# Relays.net
KiCad netlist of a schematic drawn in Altium Designer
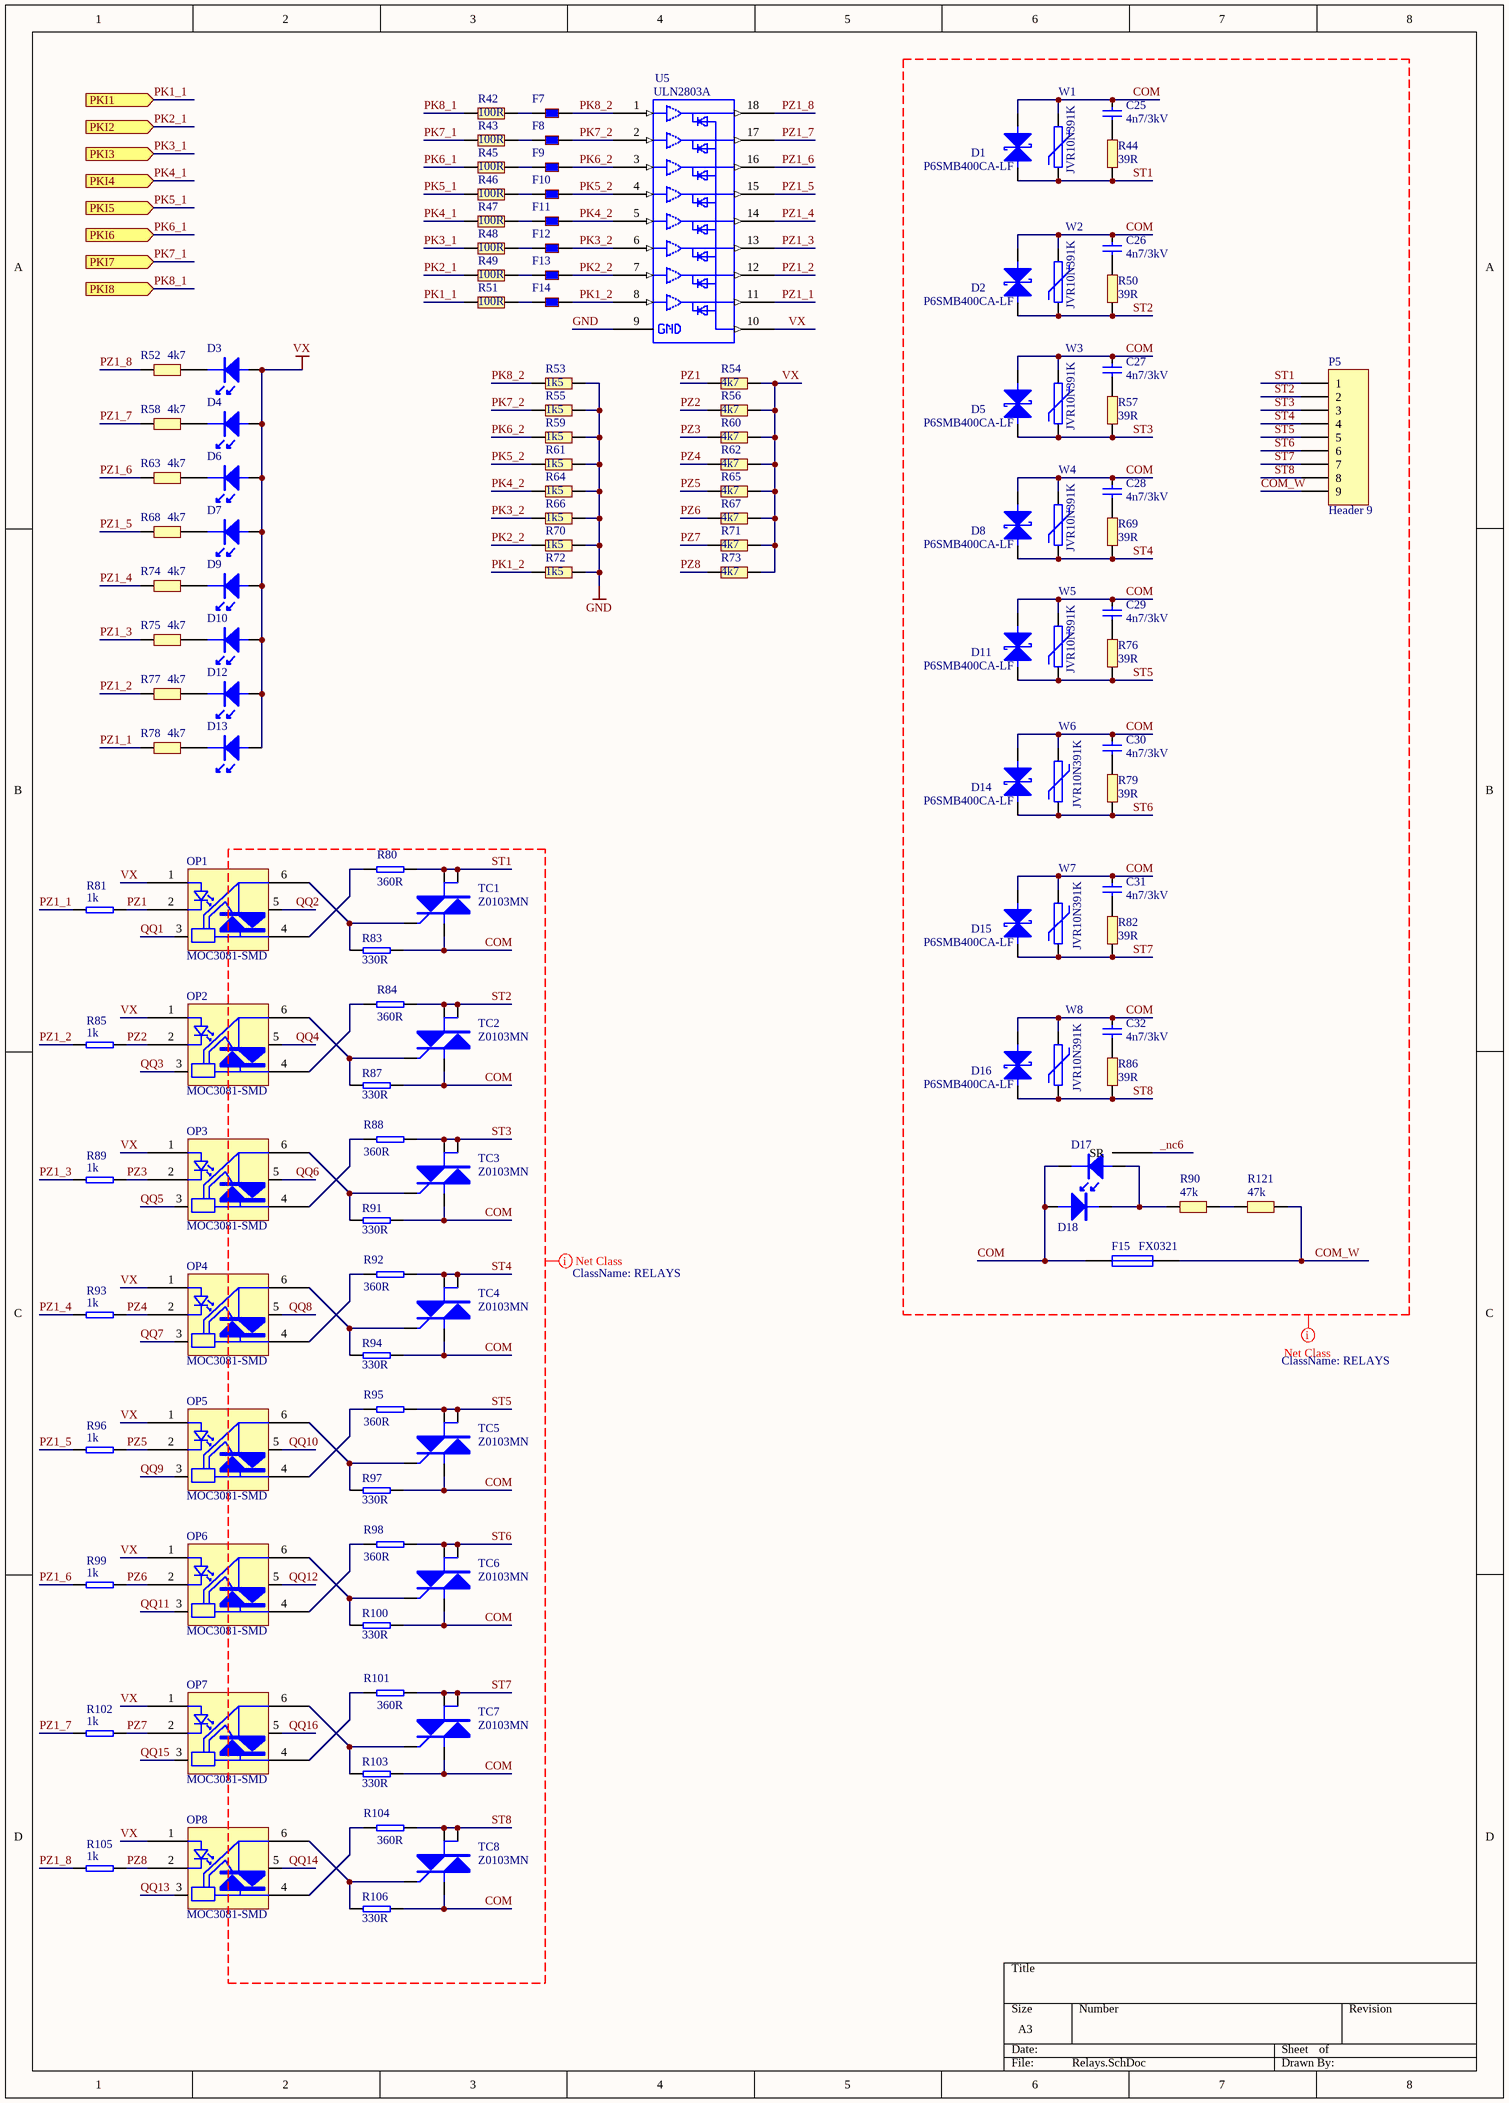
[diagram p0: Relays.SchDoc]

(export (version "E")
  (design (tool "Eeschema 10.0.6"))
  (components
    (comp (ref "C25") (value "4n7/3kV") (footprint "CAP_75") (libsource (lib "*") (part "CAP")))
    (comp (ref "C26") (value "4n7/3kV") (footprint "CAP_75") (libsource (lib "*") (part "CAP")))
    (comp (ref "C27") (value "4n7/3kV") (footprint "CAP_75") (libsource (lib "*") (part "CAP")))
    (comp (ref "C28") (value "4n7/3kV") (footprint "CAP_75") (libsource (lib "*") (part "CAP")))
    (comp (ref "C29") (value "4n7/3kV") (footprint "CAP_75") (libsource (lib "*") (part "CAP")))
    (comp (ref "C30") (value "4n7/3kV") (footprint "CAP_75") (libsource (lib "*") (part "CAP")))
    (comp (ref "C31") (value "4n7/3kV") (footprint "CAP_75") (libsource (lib "*") (part "CAP")))
    (comp (ref "C32") (value "4n7/3kV") (footprint "CAP_75") (libsource (lib "*") (part "CAP")))
    (comp (ref "D1")
      (value "P6SMB400CA-LF")
      (footprint "RD5_U")
      (libsource (lib "ElhosSchLib") (part "TRANSIL"))
    )
    (comp (ref "D2")
      (value "P6SMB400CA-LF")
      (footprint "RD5_U")
      (libsource (lib "ElhosSchLib") (part "TRANSIL"))
    )
    (comp (ref "D3") (value "LED1") (footprint "0805LB") (libsource (lib "ElhosSchLib") (part "LED1")))
    (comp (ref "D4") (value "LED1") (footprint "0805LB") (libsource (lib "ElhosSchLib") (part "LED1")))
    (comp (ref "D5")
      (value "P6SMB400CA-LF")
      (footprint "RD5_U")
      (libsource (lib "ElhosSchLib") (part "TRANSIL"))
    )
    (comp (ref "D6") (value "LED1") (footprint "0805LB") (libsource (lib "ElhosSchLib") (part "LED1")))
    (comp (ref "D7") (value "LED1") (footprint "0805LB") (libsource (lib "ElhosSchLib") (part "LED1")))
    (comp (ref "D8")
      (value "P6SMB400CA-LF")
      (footprint "RD5_U")
      (libsource (lib "ElhosSchLib") (part "TRANSIL"))
    )
    (comp (ref "D9") (value "LED1") (footprint "0805LB") (libsource (lib "ElhosSchLib") (part "LED1")))
    (comp (ref "D10") (value "LED1") (footprint "0805LB") (libsource (lib "ElhosSchLib") (part "LED1")))
    (comp (ref "D11")
      (value "P6SMB400CA-LF")
      (footprint "RD5_U")
      (libsource (lib "ElhosSchLib") (part "TRANSIL"))
    )
    (comp (ref "D12") (value "LED1") (footprint "0805LB") (libsource (lib "ElhosSchLib") (part "LED1")))
    (comp (ref "D13") (value "LED1") (footprint "0805LB") (libsource (lib "ElhosSchLib") (part "LED1")))
    (comp (ref "D14")
      (value "P6SMB400CA-LF")
      (footprint "RD5_U")
      (libsource (lib "ElhosSchLib") (part "TRANSIL"))
    )
    (comp (ref "D15")
      (value "P6SMB400CA-LF")
      (footprint "RD5_U")
      (libsource (lib "ElhosSchLib") (part "TRANSIL"))
    )
    (comp (ref "D16")
      (value "P6SMB400CA-LF")
      (footprint "RD5_U")
      (libsource (lib "ElhosSchLib") (part "TRANSIL"))
    )
    (comp (ref "D17") (value "LED1") (footprint "LED_LAMP_1") (libsource (lib "") (part "LED1_1")))
    (comp (ref "D18")
      (value "1N4148-0805")
      (footprint "0805D")
      (description "Diode")
      (libsource (lib "*") (part "DIODE1"))
    )
    (comp (ref "F7")
      (value "BLM18AG102SN1D")
      (footprint "0603L")
      (description "Koralik ferrytowy")
      (libsource (lib "*") (part "KORALIK"))
    )
    (comp (ref "F8")
      (value "BLM18AG102SN1D")
      (footprint "0603L")
      (description "Koralik ferrytowy")
      (libsource (lib "*") (part "KORALIK"))
    )
    (comp (ref "F9")
      (value "BLM18AG102SN1D")
      (footprint "0603L")
      (description "Koralik ferrytowy")
      (libsource (lib "*") (part "KORALIK"))
    )
    (comp (ref "F10")
      (value "BLM18AG102SN1D")
      (footprint "0603L")
      (description "Koralik ferrytowy")
      (libsource (lib "*") (part "KORALIK"))
    )
    (comp (ref "F11")
      (value "BLM18AG102SN1D")
      (footprint "0603L")
      (description "Koralik ferrytowy")
      (libsource (lib "*") (part "KORALIK"))
    )
    (comp (ref "F12")
      (value "BLM18AG102SN1D")
      (footprint "0603L")
      (description "Koralik ferrytowy")
      (libsource (lib "*") (part "KORALIK"))
    )
    (comp (ref "F13")
      (value "BLM18AG102SN1D")
      (footprint "0603L")
      (description "Koralik ferrytowy")
      (libsource (lib "*") (part "KORALIK"))
    )
    (comp (ref "F14")
      (value "BLM18AG102SN1D")
      (footprint "0603L")
      (description "Koralik ferrytowy")
      (libsource (lib "*") (part "KORALIK"))
    )
    (comp (ref "F15")
      (value "FX0321")
      (footprint "FX300")
      (description "Fuse")
      (libsource (lib "*") (part "FUSE1"))
    )
    (comp (ref "OP1")
      (value "MOC3081-SMD")
      (footprint "SMD6-OP")
      (libsource (lib "ElhosSchLib") (part "MOC3041"))
    )
    (comp (ref "OP2")
      (value "MOC3081-SMD")
      (footprint "SMD6-OP")
      (libsource (lib "ElhosSchLib") (part "MOC3041"))
    )
    (comp (ref "OP3")
      (value "MOC3081-SMD")
      (footprint "SMD6-OP")
      (libsource (lib "ElhosSchLib") (part "MOC3041"))
    )
    (comp (ref "OP4")
      (value "MOC3081-SMD")
      (footprint "SMD6-OP")
      (libsource (lib "ElhosSchLib") (part "MOC3041"))
    )
    (comp (ref "OP5")
      (value "MOC3081-SMD")
      (footprint "SMD6-OP")
      (libsource (lib "ElhosSchLib") (part "MOC3041"))
    )
    (comp (ref "OP6")
      (value "MOC3081-SMD")
      (footprint "SMD6-OP")
      (libsource (lib "ElhosSchLib") (part "MOC3041"))
    )
    (comp (ref "OP7")
      (value "MOC3081-SMD")
      (footprint "SMD6-OP")
      (libsource (lib "ElhosSchLib") (part "MOC3041"))
    )
    (comp (ref "OP8")
      (value "MOC3081-SMD")
      (footprint "SMD6-OP")
      (libsource (lib "ElhosSchLib") (part "MOC3041"))
    )
    (comp (ref "P5")
      (value "Header 9")
      (description "Header, 9-Pin")
      (fields (field (name "PUBLISHER") "Altium Limited"))
      (libsource (lib "Miscellaneous Connectors") (part "Header 9"))
    )
    (comp (ref "R42") (value "100R") (footprint "0603R") (libsource (lib "") (part "RES3_1")))
    (comp (ref "R43") (value "100R") (footprint "0603R") (libsource (lib "") (part "RES3_1")))
    (comp (ref "R44") (value "39R") (footprint "1206") (libsource (lib "") (part "RES3_2")))
    (comp (ref "R45") (value "100R") (footprint "0603R") (libsource (lib "") (part "RES3_1")))
    (comp (ref "R46") (value "100R") (footprint "0603R") (libsource (lib "") (part "RES3_1")))
    (comp (ref "R47") (value "100R") (footprint "0603R") (libsource (lib "") (part "RES3_1")))
    (comp (ref "R48") (value "100R") (footprint "0603R") (libsource (lib "") (part "RES3_1")))
    (comp (ref "R49") (value "100R") (footprint "0603R") (libsource (lib "") (part "RES3_1")))
    (comp (ref "R50") (value "39R") (footprint "1206") (libsource (lib "") (part "RES3_2")))
    (comp (ref "R51") (value "100R") (footprint "0603R") (libsource (lib "") (part "RES3_1")))
    (comp (ref "R52") (value "4k7") (footprint "0603R") (libsource (lib "") (part "RES3_1")))
    (comp (ref "R53") (value "1k5") (footprint "0603R") (libsource (lib "") (part "RES3_1")))
    (comp (ref "R54") (value "4k7") (footprint "0603R") (libsource (lib "") (part "RES3_1")))
    (comp (ref "R55") (value "1k5") (footprint "0603R") (libsource (lib "") (part "RES3_1")))
    (comp (ref "R56") (value "4k7") (footprint "0603R") (libsource (lib "") (part "RES3_1")))
    (comp (ref "R57") (value "39R") (footprint "1206") (libsource (lib "") (part "RES3_2")))
    (comp (ref "R58") (value "4k7") (footprint "0603R") (libsource (lib "") (part "RES3_1")))
    (comp (ref "R59") (value "1k5") (footprint "0603R") (libsource (lib "") (part "RES3_1")))
    (comp (ref "R60") (value "4k7") (footprint "0603R") (libsource (lib "") (part "RES3_1")))
    (comp (ref "R61") (value "1k5") (footprint "0603R") (libsource (lib "") (part "RES3_1")))
    (comp (ref "R62") (value "4k7") (footprint "0603R") (libsource (lib "") (part "RES3_1")))
    (comp (ref "R63") (value "4k7") (footprint "0603R") (libsource (lib "") (part "RES3_1")))
    (comp (ref "R64") (value "1k5") (footprint "0603R") (libsource (lib "") (part "RES3_1")))
    (comp (ref "R65") (value "4k7") (footprint "0603R") (libsource (lib "") (part "RES3_1")))
    (comp (ref "R66") (value "1k5") (footprint "0603R") (libsource (lib "") (part "RES3_1")))
    (comp (ref "R67") (value "4k7") (footprint "0603R") (libsource (lib "") (part "RES3_1")))
    (comp (ref "R68") (value "4k7") (footprint "0603R") (libsource (lib "") (part "RES3_1")))
    (comp (ref "R69") (value "39R") (footprint "1206") (libsource (lib "") (part "RES3_2")))
    (comp (ref "R70") (value "1k5") (footprint "0603R") (libsource (lib "") (part "RES3_1")))
    (comp (ref "R71") (value "4k7") (footprint "0603R") (libsource (lib "") (part "RES3_1")))
    (comp (ref "R72") (value "1k5") (footprint "0603R") (libsource (lib "") (part "RES3_1")))
    (comp (ref "R73") (value "4k7") (footprint "0603R") (libsource (lib "") (part "RES3_1")))
    (comp (ref "R74") (value "4k7") (footprint "0603R") (libsource (lib "") (part "RES3_1")))
    (comp (ref "R75") (value "4k7") (footprint "0603R") (libsource (lib "") (part "RES3_1")))
    (comp (ref "R76") (value "39R") (footprint "1206") (libsource (lib "") (part "RES3_2")))
    (comp (ref "R77") (value "4k7") (footprint "0603R") (libsource (lib "") (part "RES3_1")))
    (comp (ref "R78") (value "4k7") (footprint "0603R") (libsource (lib "") (part "RES3_1")))
    (comp (ref "R79") (value "39R") (footprint "1206") (libsource (lib "") (part "RES3_2")))
    (comp (ref "R80") (value "360R") (footprint "0805R") (libsource (lib "*") (part "RES3")))
    (comp (ref "R81") (value "1k") (footprint "0603R") (libsource (lib "*") (part "RES3")))
    (comp (ref "R82") (value "39R") (footprint "1206") (libsource (lib "") (part "RES3_2")))
    (comp (ref "R83") (value "330R") (footprint "0805R") (libsource (lib "*") (part "RES3")))
    (comp (ref "R84") (value "360R") (footprint "0805R") (libsource (lib "*") (part "RES3")))
    (comp (ref "R85") (value "1k") (footprint "0603R") (libsource (lib "*") (part "RES3")))
    (comp (ref "R86") (value "39R") (footprint "1206") (libsource (lib "") (part "RES3_2")))
    (comp (ref "R87") (value "330R") (footprint "0805R") (libsource (lib "*") (part "RES3")))
    (comp (ref "R88") (value "360R") (footprint "0805R") (libsource (lib "*") (part "RES3")))
    (comp (ref "R89") (value "1k") (footprint "0603R") (libsource (lib "*") (part "RES3")))
    (comp (ref "R90") (value "47k") (footprint "1206") (libsource (lib "") (part "RES3_1")))
    (comp (ref "R91") (value "330R") (footprint "0805R") (libsource (lib "*") (part "RES3")))
    (comp (ref "R92") (value "360R") (footprint "0805R") (libsource (lib "*") (part "RES3")))
    (comp (ref "R93") (value "1k") (footprint "0603R") (libsource (lib "*") (part "RES3")))
    (comp (ref "R94") (value "330R") (footprint "0805R") (libsource (lib "*") (part "RES3")))
    (comp (ref "R95") (value "360R") (footprint "0805R") (libsource (lib "*") (part "RES3")))
    (comp (ref "R96") (value "1k") (footprint "0603R") (libsource (lib "*") (part "RES3")))
    (comp (ref "R97") (value "330R") (footprint "0805R") (libsource (lib "*") (part "RES3")))
    (comp (ref "R98") (value "360R") (footprint "0805R") (libsource (lib "*") (part "RES3")))
    (comp (ref "R99") (value "1k") (footprint "0603R") (libsource (lib "*") (part "RES3")))
    (comp (ref "R100") (value "330R") (footprint "0805R") (libsource (lib "*") (part "RES3")))
    (comp (ref "R101") (value "360R") (footprint "0805R") (libsource (lib "*") (part "RES3")))
    (comp (ref "R102") (value "1k") (footprint "0603R") (libsource (lib "*") (part "RES3")))
    (comp (ref "R103") (value "330R") (footprint "0805R") (libsource (lib "*") (part "RES3")))
    (comp (ref "R104") (value "360R") (footprint "0805R") (libsource (lib "*") (part "RES3")))
    (comp (ref "R105") (value "1k") (footprint "0603R") (libsource (lib "*") (part "RES3")))
    (comp (ref "R106") (value "330R") (footprint "0805R") (libsource (lib "*") (part "RES3")))
    (comp (ref "R121") (value "47k") (footprint "1206") (libsource (lib "") (part "RES3_1")))
    (comp (ref "TC1") (value "Z0103MN") (footprint "SOT223") (libsource (lib "*") (part "Z0103MN")))
    (comp (ref "TC2") (value "Z0103MN") (footprint "SOT223") (libsource (lib "*") (part "Z0103MN")))
    (comp (ref "TC3") (value "Z0103MN") (footprint "SOT223") (libsource (lib "*") (part "Z0103MN")))
    (comp (ref "TC4") (value "Z0103MN") (footprint "SOT223") (libsource (lib "*") (part "Z0103MN")))
    (comp (ref "TC5") (value "Z0103MN") (footprint "SOT223") (libsource (lib "*") (part "Z0103MN")))
    (comp (ref "TC6") (value "Z0103MN") (footprint "SOT223") (libsource (lib "*") (part "Z0103MN")))
    (comp (ref "TC7") (value "Z0103MN") (footprint "SOT223") (libsource (lib "*") (part "Z0103MN")))
    (comp (ref "TC8") (value "Z0103MN") (footprint "SOT223") (libsource (lib "*") (part "Z0103MN")))
    (comp (ref "U5")
      (value "ULN2803A")
      (footprint "SO-18")
      (libsource (lib "*") (part "Pro31.tmp_ULN2803A_42"))
    )
    (comp (ref "W1") (value "JVR10N391K") (footprint "CAP_75") (libsource (lib "*") (part "RES4")))
    (comp (ref "W2") (value "JVR10N391K") (footprint "CAP_75") (libsource (lib "*") (part "RES4")))
    (comp (ref "W3") (value "JVR10N391K") (footprint "CAP_75") (libsource (lib "*") (part "RES4")))
    (comp (ref "W4") (value "JVR10N391K") (footprint "CAP_75") (libsource (lib "*") (part "RES4")))
    (comp (ref "W5") (value "JVR10N391K") (footprint "CAP_75") (libsource (lib "*") (part "RES4")))
    (comp (ref "W6") (value "JVR10N391K") (footprint "CAP_75") (libsource (lib "*") (part "RES4")))
    (comp (ref "W7") (value "JVR10N391K") (footprint "CAP_75") (libsource (lib "*") (part "RES4")))
    (comp (ref "W8") (value "JVR10N391K") (footprint "CAP_75") (libsource (lib "*") (part "RES4")))
  )
  (nets
    (net (code "1") (name "/COM") (class "Default")
      (node (ref "C25") (pin "2") (pintype "passive"))
      (node (ref "C26") (pin "2") (pintype "passive"))
      (node (ref "C27") (pin "2") (pintype "passive"))
      (node (ref "C28") (pin "2") (pintype "passive"))
      (node (ref "C29") (pin "2") (pintype "passive"))
      (node (ref "C30") (pin "2") (pintype "passive"))
      (node (ref "C31") (pin "2") (pintype "passive"))
      (node (ref "C32") (pin "2") (pintype "passive"))
      (node (ref "D1") (pin "K") (pinfunction "K_K") (pintype "passive"))
      (node (ref "D11") (pin "K") (pinfunction "K_K") (pintype "passive"))
      (node (ref "D14") (pin "K") (pinfunction "K_K") (pintype "passive"))
      (node (ref "D15") (pin "K") (pinfunction "K_K") (pintype "passive"))
      (node (ref "D16") (pin "K") (pinfunction "K_K") (pintype "passive"))
      (node (ref "D17") (pin "K") (pinfunction "2_K") (pintype "passive"))
      (node (ref "D18") (pin "A") (pinfunction "A_A") (pintype "passive"))
      (node (ref "D2") (pin "K") (pinfunction "K_K") (pintype "passive"))
      (node (ref "D5") (pin "K") (pinfunction "K_K") (pintype "passive"))
      (node (ref "D8") (pin "K") (pinfunction "K_K") (pintype "passive"))
      (node (ref "F15") (pin "1") (pinfunction "1_1") (pintype "passive"))
      (node (ref "R100") (pin "1") (pintype "passive"))
      (node (ref "R103") (pin "1") (pintype "passive"))
      (node (ref "R106") (pin "1") (pintype "passive"))
      (node (ref "R83") (pin "1") (pintype "passive"))
      (node (ref "R87") (pin "1") (pintype "passive"))
      (node (ref "R91") (pin "1") (pintype "passive"))
      (node (ref "R94") (pin "1") (pintype "passive"))
      (node (ref "R97") (pin "1") (pintype "passive"))
      (node (ref "TC1") (pin "1") (pintype "passive"))
      (node (ref "TC2") (pin "1") (pintype "passive"))
      (node (ref "TC3") (pin "1") (pintype "passive"))
      (node (ref "TC4") (pin "1") (pintype "passive"))
      (node (ref "TC5") (pin "1") (pintype "passive"))
      (node (ref "TC6") (pin "1") (pintype "passive"))
      (node (ref "TC7") (pin "1") (pintype "passive"))
      (node (ref "TC8") (pin "1") (pintype "passive"))
      (node (ref "W1") (pin "1") (pintype "passive"))
      (node (ref "W2") (pin "1") (pintype "passive"))
      (node (ref "W3") (pin "1") (pintype "passive"))
      (node (ref "W4") (pin "1") (pintype "passive"))
      (node (ref "W5") (pin "1") (pintype "passive"))
      (node (ref "W6") (pin "1") (pintype "passive"))
      (node (ref "W7") (pin "1") (pintype "passive"))
      (node (ref "W8") (pin "1") (pintype "passive"))
    )
    (net (code "2") (name "/COM_W") (class "Default")
      (node (ref "F15") (pin "2") (pinfunction "2_2") (pintype "passive"))
      (node (ref "P5") (pin "9") (pinfunction "9_9") (pintype "passive"))
      (node (ref "R121") (pin "1") (pintype "passive"))
    )
    (net (code "3") (name "/PK1_1") (class "Default") (node (ref "R51") (pin "2") (pintype "passive")))
    (net (code "4") (name "/PK1_2") (class "Default")
      (node (ref "F14") (pin "2") (pintype "passive"))
      (node (ref "R72") (pin "2") (pintype "passive"))
      (node (ref "U5") (pin "8") (pintype "input"))
    )
    (net (code "5") (name "/PK2_1") (class "Default") (node (ref "R49") (pin "2") (pintype "passive")))
    (net (code "6") (name "/PK2_2") (class "Default")
      (node (ref "F13") (pin "2") (pintype "passive"))
      (node (ref "R70") (pin "2") (pintype "passive"))
      (node (ref "U5") (pin "7") (pintype "input"))
    )
    (net (code "7") (name "/PK3_1") (class "Default") (node (ref "R48") (pin "2") (pintype "passive")))
    (net (code "8") (name "/PK3_2") (class "Default")
      (node (ref "F12") (pin "2") (pintype "passive"))
      (node (ref "R66") (pin "2") (pintype "passive"))
      (node (ref "U5") (pin "6") (pintype "input"))
    )
    (net (code "9") (name "/PK4_1") (class "Default") (node (ref "R47") (pin "2") (pintype "passive")))
    (net (code "10") (name "/PK4_2") (class "Default")
      (node (ref "F11") (pin "2") (pintype "passive"))
      (node (ref "R64") (pin "2") (pintype "passive"))
      (node (ref "U5") (pin "5") (pintype "input"))
    )
    (net (code "11") (name "/PK5_1") (class "Default") (node (ref "R46") (pin "2") (pintype "passive")))
    (net (code "12") (name "/PK5_2") (class "Default")
      (node (ref "F10") (pin "2") (pintype "passive"))
      (node (ref "R61") (pin "2") (pintype "passive"))
      (node (ref "U5") (pin "4") (pintype "input"))
    )
    (net (code "13") (name "/PK6_1") (class "Default") (node (ref "R45") (pin "2") (pintype "passive")))
    (net (code "14") (name "/PK6_2") (class "Default")
      (node (ref "F9") (pin "2") (pintype "passive"))
      (node (ref "R59") (pin "2") (pintype "passive"))
      (node (ref "U5") (pin "3") (pintype "input"))
    )
    (net (code "15") (name "/PK7_1") (class "Default") (node (ref "R43") (pin "2") (pintype "passive")))
    (net (code "16") (name "/PK7_2") (class "Default")
      (node (ref "F8") (pin "2") (pintype "passive"))
      (node (ref "R55") (pin "2") (pintype "passive"))
      (node (ref "U5") (pin "2") (pintype "input"))
    )
    (net (code "17") (name "/PK8_1") (class "Default") (node (ref "R42") (pin "2") (pintype "passive")))
    (net (code "18") (name "/PK8_2") (class "Default")
      (node (ref "F7") (pin "2") (pintype "passive"))
      (node (ref "R53") (pin "2") (pintype "passive"))
      (node (ref "U5") (pin "1") (pintype "input"))
    )
    (net (code "19") (name "/PZ1") (class "Default")
      (node (ref "OP1") (pin "2") (pintype "passive"))
      (node (ref "R54") (pin "2") (pintype "passive"))
      (node (ref "R81") (pin "2") (pintype "passive"))
    )
    (net (code "20") (name "/PZ1_1") (class "Default")
      (node (ref "R78") (pin "2") (pintype "passive"))
      (node (ref "R81") (pin "1") (pintype "passive"))
      (node (ref "U5") (pin "11") (pintype "output"))
    )
    (net (code "21") (name "/PZ1_2") (class "Default")
      (node (ref "R77") (pin "2") (pintype "passive"))
      (node (ref "R85") (pin "1") (pintype "passive"))
      (node (ref "U5") (pin "12") (pintype "output"))
    )
    (net (code "22") (name "/PZ1_3") (class "Default")
      (node (ref "R75") (pin "2") (pintype "passive"))
      (node (ref "R89") (pin "1") (pintype "passive"))
      (node (ref "U5") (pin "13") (pintype "output"))
    )
    (net (code "23") (name "/PZ1_4") (class "Default")
      (node (ref "R74") (pin "2") (pintype "passive"))
      (node (ref "R93") (pin "1") (pintype "passive"))
      (node (ref "U5") (pin "14") (pintype "output"))
    )
    (net (code "24") (name "/PZ1_5") (class "Default")
      (node (ref "R68") (pin "2") (pintype "passive"))
      (node (ref "R96") (pin "1") (pintype "passive"))
      (node (ref "U5") (pin "15") (pintype "output"))
    )
    (net (code "25") (name "/PZ1_6") (class "Default")
      (node (ref "R63") (pin "2") (pintype "passive"))
      (node (ref "R99") (pin "1") (pintype "passive"))
      (node (ref "U5") (pin "16") (pintype "output"))
    )
    (net (code "26") (name "/PZ1_7") (class "Default")
      (node (ref "R102") (pin "1") (pintype "passive"))
      (node (ref "R58") (pin "2") (pintype "passive"))
      (node (ref "U5") (pin "17") (pintype "output"))
    )
    (net (code "27") (name "/PZ1_8") (class "Default")
      (node (ref "R105") (pin "1") (pintype "passive"))
      (node (ref "R52") (pin "2") (pintype "passive"))
      (node (ref "U5") (pin "18") (pintype "output"))
    )
    (net (code "28") (name "/PZ2") (class "Default")
      (node (ref "OP2") (pin "2") (pintype "passive"))
      (node (ref "R56") (pin "2") (pintype "passive"))
      (node (ref "R85") (pin "2") (pintype "passive"))
    )
    (net (code "29") (name "/PZ3") (class "Default")
      (node (ref "OP3") (pin "2") (pintype "passive"))
      (node (ref "R60") (pin "2") (pintype "passive"))
      (node (ref "R89") (pin "2") (pintype "passive"))
    )
    (net (code "30") (name "/PZ4") (class "Default")
      (node (ref "OP4") (pin "2") (pintype "passive"))
      (node (ref "R62") (pin "2") (pintype "passive"))
      (node (ref "R93") (pin "2") (pintype "passive"))
    )
    (net (code "31") (name "/PZ5") (class "Default")
      (node (ref "OP5") (pin "2") (pintype "passive"))
      (node (ref "R65") (pin "2") (pintype "passive"))
      (node (ref "R96") (pin "2") (pintype "passive"))
    )
    (net (code "32") (name "/PZ6") (class "Default")
      (node (ref "OP6") (pin "2") (pintype "passive"))
      (node (ref "R67") (pin "2") (pintype "passive"))
      (node (ref "R99") (pin "2") (pintype "passive"))
    )
    (net (code "33") (name "/PZ7") (class "Default")
      (node (ref "OP7") (pin "2") (pintype "passive"))
      (node (ref "R102") (pin "2") (pintype "passive"))
      (node (ref "R71") (pin "2") (pintype "passive"))
    )
    (net (code "34") (name "/PZ8") (class "Default")
      (node (ref "OP8") (pin "2") (pintype "passive"))
      (node (ref "R105") (pin "2") (pintype "passive"))
      (node (ref "R73") (pin "2") (pintype "passive"))
    )
    (net (code "35") (name "/QQ1") (class "Default") (node (ref "OP1") (pin "3") (pintype "passive")))
    (net (code "36") (name "/QQ2") (class "Default") (node (ref "OP1") (pin "5") (pintype "passive")))
    (net (code "37") (name "/QQ3") (class "Default") (node (ref "OP2") (pin "3") (pintype "passive")))
    (net (code "38") (name "/QQ4") (class "Default") (node (ref "OP2") (pin "5") (pintype "passive")))
    (net (code "39") (name "/QQ5") (class "Default") (node (ref "OP3") (pin "3") (pintype "passive")))
    (net (code "40") (name "/QQ6") (class "Default") (node (ref "OP3") (pin "5") (pintype "passive")))
    (net (code "41") (name "/QQ7") (class "Default") (node (ref "OP4") (pin "3") (pintype "passive")))
    (net (code "42") (name "/QQ8") (class "Default") (node (ref "OP4") (pin "5") (pintype "passive")))
    (net (code "43") (name "/QQ9") (class "Default") (node (ref "OP5") (pin "3") (pintype "passive")))
    (net (code "44") (name "/QQ10") (class "Default") (node (ref "OP5") (pin "5") (pintype "passive")))
    (net (code "45") (name "/QQ11") (class "Default") (node (ref "OP6") (pin "3") (pintype "passive")))
    (net (code "46") (name "/QQ12") (class "Default") (node (ref "OP6") (pin "5") (pintype "passive")))
    (net (code "47") (name "/QQ13") (class "Default") (node (ref "OP8") (pin "3") (pintype "passive")))
    (net (code "48") (name "/QQ14") (class "Default") (node (ref "OP8") (pin "5") (pintype "passive")))
    (net (code "49") (name "/QQ15") (class "Default") (node (ref "OP7") (pin "3") (pintype "passive")))
    (net (code "50") (name "/QQ16") (class "Default") (node (ref "OP7") (pin "5") (pintype "passive")))
    (net (code "51") (name "/ST1") (class "Default")
      (node (ref "D1") (pin "A") (pinfunction "A_A") (pintype "passive"))
      (node (ref "P5") (pin "1") (pinfunction "1_1") (pintype "passive"))
      (node (ref "R44") (pin "1") (pintype "passive"))
      (node (ref "R80") (pin "2") (pintype "passive"))
      (node (ref "TC1") (pin "2") (pintype "passive"))
      (node (ref "TC1") (pin "4") (pintype "passive"))
      (node (ref "W1") (pin "2") (pintype "passive"))
    )
    (net (code "52") (name "/ST2") (class "Default")
      (node (ref "D2") (pin "A") (pinfunction "A_A") (pintype "passive"))
      (node (ref "P5") (pin "2") (pinfunction "2_2") (pintype "passive"))
      (node (ref "R50") (pin "1") (pintype "passive"))
      (node (ref "R84") (pin "2") (pintype "passive"))
      (node (ref "TC2") (pin "2") (pintype "passive"))
      (node (ref "TC2") (pin "4") (pintype "passive"))
      (node (ref "W2") (pin "2") (pintype "passive"))
    )
    (net (code "53") (name "/ST3") (class "Default")
      (node (ref "D5") (pin "A") (pinfunction "A_A") (pintype "passive"))
      (node (ref "P5") (pin "3") (pinfunction "3_3") (pintype "passive"))
      (node (ref "R57") (pin "1") (pintype "passive"))
      (node (ref "R88") (pin "2") (pintype "passive"))
      (node (ref "TC3") (pin "2") (pintype "passive"))
      (node (ref "TC3") (pin "4") (pintype "passive"))
      (node (ref "W3") (pin "2") (pintype "passive"))
    )
    (net (code "54") (name "/ST4") (class "Default")
      (node (ref "D8") (pin "A") (pinfunction "A_A") (pintype "passive"))
      (node (ref "P5") (pin "4") (pinfunction "4_4") (pintype "passive"))
      (node (ref "R69") (pin "1") (pintype "passive"))
      (node (ref "R92") (pin "2") (pintype "passive"))
      (node (ref "TC4") (pin "2") (pintype "passive"))
      (node (ref "TC4") (pin "4") (pintype "passive"))
      (node (ref "W4") (pin "2") (pintype "passive"))
    )
    (net (code "55") (name "/ST5") (class "Default")
      (node (ref "D11") (pin "A") (pinfunction "A_A") (pintype "passive"))
      (node (ref "P5") (pin "5") (pinfunction "5_5") (pintype "passive"))
      (node (ref "R76") (pin "1") (pintype "passive"))
      (node (ref "R95") (pin "2") (pintype "passive"))
      (node (ref "TC5") (pin "2") (pintype "passive"))
      (node (ref "TC5") (pin "4") (pintype "passive"))
      (node (ref "W5") (pin "2") (pintype "passive"))
    )
    (net (code "56") (name "/ST6") (class "Default")
      (node (ref "D14") (pin "A") (pinfunction "A_A") (pintype "passive"))
      (node (ref "P5") (pin "6") (pinfunction "6_6") (pintype "passive"))
      (node (ref "R79") (pin "1") (pintype "passive"))
      (node (ref "R98") (pin "2") (pintype "passive"))
      (node (ref "TC6") (pin "2") (pintype "passive"))
      (node (ref "TC6") (pin "4") (pintype "passive"))
      (node (ref "W6") (pin "2") (pintype "passive"))
    )
    (net (code "57") (name "/ST7") (class "Default")
      (node (ref "D15") (pin "A") (pinfunction "A_A") (pintype "passive"))
      (node (ref "P5") (pin "7") (pinfunction "7_7") (pintype "passive"))
      (node (ref "R101") (pin "2") (pintype "passive"))
      (node (ref "R82") (pin "1") (pintype "passive"))
      (node (ref "TC7") (pin "2") (pintype "passive"))
      (node (ref "TC7") (pin "4") (pintype "passive"))
      (node (ref "W7") (pin "2") (pintype "passive"))
    )
    (net (code "58") (name "/ST8") (class "Default")
      (node (ref "D16") (pin "A") (pinfunction "A_A") (pintype "passive"))
      (node (ref "P5") (pin "8") (pinfunction "8_8") (pintype "passive"))
      (node (ref "R104") (pin "2") (pintype "passive"))
      (node (ref "R86") (pin "1") (pintype "passive"))
      (node (ref "TC8") (pin "2") (pintype "passive"))
      (node (ref "TC8") (pin "4") (pintype "passive"))
      (node (ref "W8") (pin "2") (pintype "passive"))
    )
    (net (code "59") (name "/_nc6") (class "Default")
      (node (ref "D17") (pin "0") (pinfunction "SR_0") (pintype "passive"))
    )
    (net (code "60") (name "GND") (class "Default")
      (node (ref "R53") (pin "1") (pintype "passive"))
      (node (ref "R55") (pin "1") (pintype "passive"))
      (node (ref "R59") (pin "1") (pintype "passive"))
      (node (ref "R61") (pin "1") (pintype "passive"))
      (node (ref "R64") (pin "1") (pintype "passive"))
      (node (ref "R66") (pin "1") (pintype "passive"))
      (node (ref "R70") (pin "1") (pintype "passive"))
      (node (ref "R72") (pin "1") (pintype "passive"))
      (node (ref "U5") (pin "9") (pintype "passive"))
    )
    (net (code "61") (name "Net-(C25-Pad1)") (class "Default")
      (node (ref "C25") (pin "1") (pintype "passive"))
      (node (ref "R44") (pin "2") (pintype "passive"))
    )
    (net (code "62") (name "Net-(C26-Pad1)") (class "Default")
      (node (ref "C26") (pin "1") (pintype "passive"))
      (node (ref "R50") (pin "2") (pintype "passive"))
    )
    (net (code "63") (name "Net-(C27-Pad1)") (class "Default")
      (node (ref "C27") (pin "1") (pintype "passive"))
      (node (ref "R57") (pin "2") (pintype "passive"))
    )
    (net (code "64") (name "Net-(C28-Pad1)") (class "Default")
      (node (ref "C28") (pin "1") (pintype "passive"))
      (node (ref "R69") (pin "2") (pintype "passive"))
    )
    (net (code "65") (name "Net-(C29-Pad1)") (class "Default")
      (node (ref "C29") (pin "1") (pintype "passive"))
      (node (ref "R76") (pin "2") (pintype "passive"))
    )
    (net (code "66") (name "Net-(C30-Pad1)") (class "Default")
      (node (ref "C30") (pin "1") (pintype "passive"))
      (node (ref "R79") (pin "2") (pintype "passive"))
    )
    (net (code "67") (name "Net-(C31-Pad1)") (class "Default")
      (node (ref "C31") (pin "1") (pintype "passive"))
      (node (ref "R82") (pin "2") (pintype "passive"))
    )
    (net (code "68") (name "Net-(C32-Pad1)") (class "Default")
      (node (ref "C32") (pin "1") (pintype "passive"))
      (node (ref "R86") (pin "2") (pintype "passive"))
    )
    (net (code "69") (name "Net-(D3-2)") (class "Default")
      (node (ref "D3") (pin "K") (pinfunction "2_K") (pintype "passive"))
      (node (ref "R52") (pin "1") (pintype "passive"))
    )
    (net (code "70") (name "Net-(D4-2)") (class "Default")
      (node (ref "D4") (pin "K") (pinfunction "2_K") (pintype "passive"))
      (node (ref "R58") (pin "1") (pintype "passive"))
    )
    (net (code "71") (name "Net-(D6-2)") (class "Default")
      (node (ref "D6") (pin "K") (pinfunction "2_K") (pintype "passive"))
      (node (ref "R63") (pin "1") (pintype "passive"))
    )
    (net (code "72") (name "Net-(D7-2)") (class "Default")
      (node (ref "D7") (pin "K") (pinfunction "2_K") (pintype "passive"))
      (node (ref "R68") (pin "1") (pintype "passive"))
    )
    (net (code "73") (name "Net-(D9-2)") (class "Default")
      (node (ref "D9") (pin "K") (pinfunction "2_K") (pintype "passive"))
      (node (ref "R74") (pin "1") (pintype "passive"))
    )
    (net (code "74") (name "Net-(D10-2)") (class "Default")
      (node (ref "D10") (pin "K") (pinfunction "2_K") (pintype "passive"))
      (node (ref "R75") (pin "1") (pintype "passive"))
    )
    (net (code "75") (name "Net-(D12-2)") (class "Default")
      (node (ref "D12") (pin "K") (pinfunction "2_K") (pintype "passive"))
      (node (ref "R77") (pin "1") (pintype "passive"))
    )
    (net (code "76") (name "Net-(D13-2)") (class "Default")
      (node (ref "D13") (pin "K") (pinfunction "2_K") (pintype "passive"))
      (node (ref "R78") (pin "1") (pintype "passive"))
    )
    (net (code "77") (name "Net-(D17-1)") (class "Default")
      (node (ref "D17") (pin "A") (pinfunction "1_A") (pintype "passive"))
      (node (ref "D18") (pin "K") (pinfunction "K_K") (pintype "passive"))
      (node (ref "R90") (pin "2") (pintype "passive"))
    )
    (net (code "78") (name "Net-(F7-Pad1)") (class "Default")
      (node (ref "F7") (pin "1") (pintype "passive"))
      (node (ref "R42") (pin "1") (pintype "passive"))
    )
    (net (code "79") (name "Net-(F8-Pad1)") (class "Default")
      (node (ref "F8") (pin "1") (pintype "passive"))
      (node (ref "R43") (pin "1") (pintype "passive"))
    )
    (net (code "80") (name "Net-(F9-Pad1)") (class "Default")
      (node (ref "F9") (pin "1") (pintype "passive"))
      (node (ref "R45") (pin "1") (pintype "passive"))
    )
    (net (code "81") (name "Net-(F10-Pad1)") (class "Default")
      (node (ref "F10") (pin "1") (pintype "passive"))
      (node (ref "R46") (pin "1") (pintype "passive"))
    )
    (net (code "82") (name "Net-(F11-Pad1)") (class "Default")
      (node (ref "F11") (pin "1") (pintype "passive"))
      (node (ref "R47") (pin "1") (pintype "passive"))
    )
    (net (code "83") (name "Net-(F12-Pad1)") (class "Default")
      (node (ref "F12") (pin "1") (pintype "passive"))
      (node (ref "R48") (pin "1") (pintype "passive"))
    )
    (net (code "84") (name "Net-(F13-Pad1)") (class "Default")
      (node (ref "F13") (pin "1") (pintype "passive"))
      (node (ref "R49") (pin "1") (pintype "passive"))
    )
    (net (code "85") (name "Net-(F14-Pad1)") (class "Default")
      (node (ref "F14") (pin "1") (pintype "passive"))
      (node (ref "R51") (pin "1") (pintype "passive"))
    )
    (net (code "86") (name "Net-(OP1-Pad4)") (class "Default")
      (node (ref "OP1") (pin "4") (pintype "passive"))
      (node (ref "R80") (pin "1") (pintype "passive"))
    )
    (net (code "87") (name "Net-(OP1-Pad6)") (class "Default")
      (node (ref "OP1") (pin "6") (pintype "passive"))
      (node (ref "R83") (pin "2") (pintype "passive"))
      (node (ref "TC1") (pin "3") (pintype "passive"))
    )
    (net (code "88") (name "Net-(OP2-Pad4)") (class "Default")
      (node (ref "OP2") (pin "4") (pintype "passive"))
      (node (ref "R84") (pin "1") (pintype "passive"))
    )
    (net (code "89") (name "Net-(OP2-Pad6)") (class "Default")
      (node (ref "OP2") (pin "6") (pintype "passive"))
      (node (ref "R87") (pin "2") (pintype "passive"))
      (node (ref "TC2") (pin "3") (pintype "passive"))
    )
    (net (code "90") (name "Net-(OP3-Pad4)") (class "Default")
      (node (ref "OP3") (pin "4") (pintype "passive"))
      (node (ref "R88") (pin "1") (pintype "passive"))
    )
    (net (code "91") (name "Net-(OP3-Pad6)") (class "Default")
      (node (ref "OP3") (pin "6") (pintype "passive"))
      (node (ref "R91") (pin "2") (pintype "passive"))
      (node (ref "TC3") (pin "3") (pintype "passive"))
    )
    (net (code "92") (name "Net-(OP4-Pad4)") (class "Default")
      (node (ref "OP4") (pin "4") (pintype "passive"))
      (node (ref "R92") (pin "1") (pintype "passive"))
    )
    (net (code "93") (name "Net-(OP4-Pad6)") (class "Default")
      (node (ref "OP4") (pin "6") (pintype "passive"))
      (node (ref "R94") (pin "2") (pintype "passive"))
      (node (ref "TC4") (pin "3") (pintype "passive"))
    )
    (net (code "94") (name "Net-(OP5-Pad4)") (class "Default")
      (node (ref "OP5") (pin "4") (pintype "passive"))
      (node (ref "R95") (pin "1") (pintype "passive"))
    )
    (net (code "95") (name "Net-(OP5-Pad6)") (class "Default")
      (node (ref "OP5") (pin "6") (pintype "passive"))
      (node (ref "R97") (pin "2") (pintype "passive"))
      (node (ref "TC5") (pin "3") (pintype "passive"))
    )
    (net (code "96") (name "Net-(OP6-Pad4)") (class "Default")
      (node (ref "OP6") (pin "4") (pintype "passive"))
      (node (ref "R98") (pin "1") (pintype "passive"))
    )
    (net (code "97") (name "Net-(OP6-Pad6)") (class "Default")
      (node (ref "OP6") (pin "6") (pintype "passive"))
      (node (ref "R100") (pin "2") (pintype "passive"))
      (node (ref "TC6") (pin "3") (pintype "passive"))
    )
    (net (code "98") (name "Net-(OP7-Pad4)") (class "Default")
      (node (ref "OP7") (pin "4") (pintype "passive"))
      (node (ref "R101") (pin "1") (pintype "passive"))
    )
    (net (code "99") (name "Net-(OP7-Pad6)") (class "Default")
      (node (ref "OP7") (pin "6") (pintype "passive"))
      (node (ref "R103") (pin "2") (pintype "passive"))
      (node (ref "TC7") (pin "3") (pintype "passive"))
    )
    (net (code "100") (name "Net-(OP8-Pad4)") (class "Default")
      (node (ref "OP8") (pin "4") (pintype "passive"))
      (node (ref "R104") (pin "1") (pintype "passive"))
    )
    (net (code "101") (name "Net-(OP8-Pad6)") (class "Default")
      (node (ref "OP8") (pin "6") (pintype "passive"))
      (node (ref "R106") (pin "2") (pintype "passive"))
      (node (ref "TC8") (pin "3") (pintype "passive"))
    )
    (net (code "102") (name "Net-(R121-Pad2)") (class "Default")
      (node (ref "R121") (pin "2") (pintype "passive"))
      (node (ref "R90") (pin "1") (pintype "passive"))
    )
    (net (code "103") (name "VX") (class "Default")
      (node (ref "D10") (pin "A") (pinfunction "1_A") (pintype "passive"))
      (node (ref "D12") (pin "A") (pinfunction "1_A") (pintype "passive"))
      (node (ref "D13") (pin "A") (pinfunction "1_A") (pintype "passive"))
      (node (ref "D3") (pin "A") (pinfunction "1_A") (pintype "passive"))
      (node (ref "D4") (pin "A") (pinfunction "1_A") (pintype "passive"))
      (node (ref "D6") (pin "A") (pinfunction "1_A") (pintype "passive"))
      (node (ref "D7") (pin "A") (pinfunction "1_A") (pintype "passive"))
      (node (ref "D9") (pin "A") (pinfunction "1_A") (pintype "passive"))
      (node (ref "OP1") (pin "1") (pintype "passive"))
      (node (ref "OP2") (pin "1") (pintype "passive"))
      (node (ref "OP3") (pin "1") (pintype "passive"))
      (node (ref "OP4") (pin "1") (pintype "passive"))
      (node (ref "OP5") (pin "1") (pintype "passive"))
      (node (ref "OP6") (pin "1") (pintype "passive"))
      (node (ref "OP7") (pin "1") (pintype "passive"))
      (node (ref "OP8") (pin "1") (pintype "passive"))
      (node (ref "R54") (pin "1") (pintype "passive"))
      (node (ref "R56") (pin "1") (pintype "passive"))
      (node (ref "R60") (pin "1") (pintype "passive"))
      (node (ref "R62") (pin "1") (pintype "passive"))
      (node (ref "R65") (pin "1") (pintype "passive"))
      (node (ref "R67") (pin "1") (pintype "passive"))
      (node (ref "R71") (pin "1") (pintype "passive"))
      (node (ref "R73") (pin "1") (pintype "passive"))
      (node (ref "U5") (pin "10") (pintype "output"))
    )
  )
)
